# can.net
KiCad netlist of a schematic drawn in Altium Designer
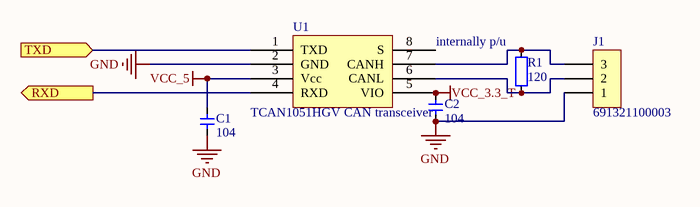
[diagram p0: can.SchDoc]

(export (version "E")
  (design (tool "Eeschema 10.0.6"))
  (components
    (comp (ref "C1")
      (value "104")
      (footprint "PCB_PassiveCap:CAP_0603")
      (description "Capacitor")
      (fields (field (name "Comment") "Cap_0603"))
      (libsource (lib "SCH_Passive") (part "Cap_0603"))
    )
    (comp (ref "C2")
      (value "104")
      (footprint "PCB_PassiveCap:CAP_0603")
      (description "Capacitor")
      (fields (field (name "Comment") "Cap_0603"))
      (libsource (lib "SCH_Passive") (part "Cap_0603"))
    )
    (comp (ref "J1")
      (value "691321100003")
      (footprint "691322110003")
      (description "WR-TBL Terminal block - serie 3211 - 3.50 mm")
      (fields
        (field (name "MANUFACTURER") "Würth Elektronik eiSos GmbH")
        (field (name "CREATED BY") "Karrer Zheng")
      )
      (libsource (lib "ALTIUM-TBL_3_50_3211_VERTICAL_PCB_HEADER_69132110000X-rev15c") (part "691321100003"))
    )
    (comp (ref "R1")
      (value "120")
      (footprint "PCB_PassiveRes:RES_0603")
      (description "Resistor")
      (fields (field (name "Comment") "Res_0603"))
      (libsource (lib "SCH_Passive") (part "Res_0603"))
    )
    (comp (ref "U1")
      (value "TCAN1051HGV CAN transceiver")
      (footprint "SOIC127P600X175-8N")
      (libsource (lib "robocart") (part "TCAN1051HGV"))
    )
  )
  (nets
    (net (code "1") (name "/RXD") (class "Default")
      (node (ref "U1") (pin "4") (pinfunction "RXD_4") (pintype "passive"))
    )
    (net (code "2") (name "/TXD") (class "Default")
      (node (ref "U1") (pin "1") (pinfunction "TXD_1") (pintype "passive"))
    )
    (net (code "3") (name "GND") (class "Default")
      (node (ref "C1") (pin "1") (pinfunction "1_1") (pintype "passive"))
      (node (ref "C2") (pin "1") (pinfunction "1_1") (pintype "passive"))
      (node (ref "J1") (pin "1") (pinfunction "1_1") (pintype "passive"))
      (node (ref "U1") (pin "2") (pinfunction "GND_2") (pintype "passive"))
    )
    (net (code "4") (name "Net-(U1-CANH)") (class "Default")
      (node (ref "J1") (pin "3") (pinfunction "3_3") (pintype "passive"))
      (node (ref "R1") (pin "2") (pinfunction "2_2") (pintype "passive"))
      (node (ref "U1") (pin "7") (pinfunction "CANH_7") (pintype "passive"))
    )
    (net (code "5") (name "Net-(U1-CANL)") (class "Default")
      (node (ref "J1") (pin "2") (pinfunction "2_2") (pintype "passive"))
      (node (ref "R1") (pin "1") (pinfunction "1_1") (pintype "passive"))
      (node (ref "U1") (pin "6") (pinfunction "CANL_6") (pintype "passive"))
    )
    (net (code "6") (name "VCC_3.3_T") (class "Default")
      (node (ref "C2") (pin "2") (pinfunction "2_2") (pintype "passive"))
      (node (ref "U1") (pin "5") (pinfunction "VIO_5") (pintype "passive"))
    )
    (net (code "7") (name "VCC_5") (class "Default")
      (node (ref "C1") (pin "2") (pinfunction "2_2") (pintype "passive"))
      (node (ref "U1") (pin "3") (pinfunction "Vcc_3") (pintype "passive"))
    )
    (net (code "8") (name "unconnected-(U1-S-Pad8)") (class "Default")
      (node (ref "U1") (pin "8") (pinfunction "S_8") (pintype "passive"))
    )
  )
)
